# power_24V.net
KiCad netlist of a schematic drawn in Altium Designer
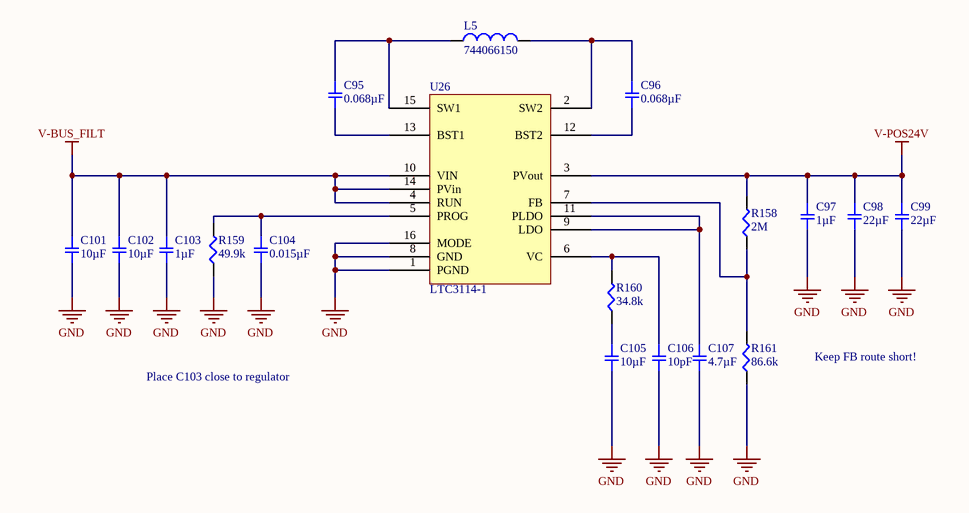
[diagram p0: power_24V.SchDoc]

(export (version "E")
  (design (tool "Eeschema 10.0.6"))
  (components
    (comp (ref "C95")
      (value "0.068µF")
      (footprint "SMD-0805C")
      (description "CAP CER 0.068UF 50V X7R 0805")
      (fields
        (field (name "DIGI-KEY PART NUMBER") "490-5807-1-ND")
        (field (name "PART NUMBER") "GCJ21BR71H683KA01L")
      )
      (libsource (lib "capacitors") (part "GCJ21BR71H683KA01L"))
    )
    (comp (ref "C96")
      (value "0.068µF")
      (footprint "SMD-0805C")
      (description "CAP CER 0.068UF 50V X7R 0805")
      (fields
        (field (name "DIGI-KEY PART NUMBER") "490-5807-1-ND")
        (field (name "PART NUMBER") "GCJ21BR71H683KA01L")
      )
      (libsource (lib "capacitors") (part "GCJ21BR71H683KA01L"))
    )
    (comp (ref "C97")
      (value "1µF")
      (footprint "SMD-0805C")
      (description "CAP CER 1UF 50V X7R 0805")
      (fields
        (field (name "DIGI-KEY PART NUMBER") "490-10667-1-ND")
        (field (name "PART NUMBER") "GCJ21BR71H105KA01L")
      )
      (libsource (lib "capacitors") (part "GCJ21BR71H105KA01L"))
    )
    (comp (ref "C98")
      (value "22µF")
      (footprint "SMD-1206C")
      (description "CAP CER 22UF 25V X5R 1206")
      (fields
        (field (name "DIGI-KEY PART NUMBER") "490-5527-1-ND")
        (field (name "PART NUMBER") "GRM31CR61E226KE15L")
      )
      (libsource (lib "capacitors") (part "GRM31CR61E226KE15L"))
    )
    (comp (ref "C99")
      (value "22µF")
      (footprint "SMD-1206C")
      (description "CAP CER 22UF 25V X5R 1206")
      (fields
        (field (name "DIGI-KEY PART NUMBER") "490-5527-1-ND")
        (field (name "PART NUMBER") "GRM31CR61E226KE15L")
      )
      (libsource (lib "capacitors") (part "GRM31CR61E226KE15L"))
    )
    (comp (ref "C101")
      (value "10µF")
      (footprint "SMD-1206C")
      (description "CAP CER 10UF 50V X5R 1206")
      (fields
        (field (name "DIGI-KEY PART NUMBER") "490-5961-1-ND")
        (field (name "PART NUMBER") "GRM31CR61H106KA12L")
      )
      (libsource (lib "capacitors") (part "GRM31CR61H106KA12L"))
    )
    (comp (ref "C102")
      (value "10µF")
      (footprint "SMD-1206C")
      (description "CAP CER 10UF 50V X5R 1206")
      (fields
        (field (name "DIGI-KEY PART NUMBER") "490-5961-1-ND")
        (field (name "PART NUMBER") "GRM31CR61H106KA12L")
      )
      (libsource (lib "capacitors") (part "GRM31CR61H106KA12L"))
    )
    (comp (ref "C103")
      (value "1µF")
      (footprint "SMD-1206C")
      (description "CAP CER 1UF 50V X7R 1206")
      (fields
        (field (name "DIGI-KEY PART NUMBER") "490-5810-1-ND")
        (field (name "PART NUMBER") "GCJ31MR71H105KA12L")
      )
      (libsource (lib "capacitors") (part "GCJ31MR71H105KA12L"))
    )
    (comp (ref "C104")
      (value "0.015µF")
      (footprint "SMD-0805C")
      (description "CAP CER 0.015UF 250V X7T 0805")
      (fields
        (field (name "DIGI-KEY PART NUMBER") "490-13987-1-ND")
        (field (name "PART NUMBER") "GC321AD72E153KX01D")
      )
      (libsource (lib "capacitors") (part "GC321AD72E153KX01D"))
    )
    (comp (ref "C105")
      (value "10µF")
      (footprint "SMD-1206C")
      (description "CAP CER 10UF 50V X5R 1206")
      (fields
        (field (name "DIGI-KEY PART NUMBER") "490-5961-1-ND")
        (field (name "PART NUMBER") "GRM31CR61H106KA12L")
      )
      (libsource (lib "capacitors") (part "GRM31CR61H106KA12L"))
    )
    (comp (ref "C106")
      (value "10pF")
      (footprint "SMD-0805C")
      (description "CAP CER 10PF 100V NP0 0805")
      (fields
        (field (name "DIGI-KEY PART NUMBER") "490-6098-1-ND")
        (field (name "PART NUMBER") "GQM2195C2A100GB01D")
      )
      (libsource (lib "capacitors") (part "GQM2195C2A100GB01D"))
    )
    (comp (ref "C107")
      (value "4.7µF")
      (footprint "SMD-1206C")
      (description "CAP CER 4.7UF 50V X7S 1206")
      (fields
        (field (name "DIGI-KEY PART NUMBER") "490-11167-1-ND")
        (field (name "PART NUMBER") "GCM31CC71H475KA03L")
      )
      (libsource (lib "capacitors") (part "GCM31CC71H475KA03L"))
    )
    (comp (ref "L5")
      (value "744066150")
      (footprint "INDP100100X38N")
      (description "FIXED IND 15UH 3.2A 50 MOHM SMD")
      (fields (field (name "MANUFACTURER") "Wurth Electronics") (field (name "TOLERANCE") "30%"))
      (libsource (lib "inductor") (part "744066150"))
    )
    (comp (ref "R158")
      (value "2M")
      (footprint "SMD-0805-RES")
      (description "RES SMD 2M OHM 1% 1/8W 0805")
      (fields
        (field (name "PART NUMBER") "ERJ-6ENF2004V")
        (field (name "DIGI-KEY PART NUMBER") "P2.00MCCT-ND")
      )
      (libsource (lib "resistors") (part "ERJ-6ENF2004V"))
    )
    (comp (ref "R159")
      (value "49.9k")
      (footprint "SMD-0805-RES")
      (description "RES SMD 49.9K OHM 1% 1/8W 0805")
      (fields
        (field (name "PART NUMBER") "ERJ-6ENF4992V")
        (field (name "DIGI-KEY PART NUMBER") "P49.9KCCT-ND")
      )
      (libsource (lib "resistors") (part "ERJ-6ENF4992V"))
    )
    (comp (ref "R160")
      (value "34.8k")
      (footprint "SMD-0805-RES")
      (description "RES SMD 34.8K OHM 1% 1/8W 0805")
      (fields
        (field (name "PART NUMBER") "ERJ-6ENF3482V")
        (field (name "DIGI-KEY PART NUMBER") "P34.8KCCT-ND")
      )
      (libsource (lib "resistors") (part "ERJ-6ENF3482V"))
    )
    (comp (ref "R161")
      (value "86.6k")
      (footprint "SMD-0805-RES")
      (description "RES SMD 86.6K OHM 1% 1/8W 0805")
      (fields
        (field (name "PART NUMBER") "ERJ-6ENF8662V")
        (field (name "DIGI-KEY PART NUMBER") "P86.6KCCT-ND")
      )
      (libsource (lib "resistors") (part "ERJ-6ENF8662V"))
    )
    (comp (ref "U26")
      (value "LTC3114-1")
      (footprint "TSOP65P640X110_HS-17N")
      (fields
        (field (name "MANUFACTURER") "Analog Devices / Linear Technology")
        (field (name "MANUFACTURER PART NUMBER") "LTC3114EFE-1#TRPBF")
      )
      (libsource (lib "ic") (part "LTC3114-1"))
    )
  )
  (nets
    (net (code "1") (name "GND") (class "Default")
      (node (ref "C101") (pin "2") (pinfunction "2_2") (pintype "passive"))
      (node (ref "C102") (pin "2") (pinfunction "2_2") (pintype "passive"))
      (node (ref "C103") (pin "2") (pinfunction "2_2") (pintype "passive"))
      (node (ref "C104") (pin "2") (pinfunction "2_2") (pintype "passive"))
      (node (ref "C105") (pin "2") (pinfunction "2_2") (pintype "passive"))
      (node (ref "C106") (pin "2") (pinfunction "2_2") (pintype "passive"))
      (node (ref "C107") (pin "2") (pinfunction "2_2") (pintype "passive"))
      (node (ref "C97") (pin "2") (pinfunction "2_2") (pintype "passive"))
      (node (ref "C98") (pin "2") (pinfunction "2_2") (pintype "passive"))
      (node (ref "C99") (pin "2") (pinfunction "2_2") (pintype "passive"))
      (node (ref "R159") (pin "1") (pinfunction "1_1") (pintype "passive"))
      (node (ref "R161") (pin "1") (pinfunction "1_1") (pintype "passive"))
      (node (ref "U26") (pin "1") (pinfunction "PGND_1") (pintype "passive"))
      (node (ref "U26") (pin "16") (pinfunction "MODE_16") (pintype "passive"))
      (node (ref "U26") (pin "8") (pinfunction "GND_8") (pintype "passive"))
    )
    (net (code "2") (name "Net-(C105-Pad1)") (class "Default")
      (node (ref "C105") (pin "1") (pinfunction "1_1") (pintype "passive"))
      (node (ref "R160") (pin "1") (pinfunction "1_1") (pintype "passive"))
    )
    (net (code "3") (name "Net-(U26-BST1)") (class "Default")
      (node (ref "C95") (pin "2") (pinfunction "2_2") (pintype "passive"))
      (node (ref "U26") (pin "13") (pinfunction "BST1_13") (pintype "passive"))
    )
    (net (code "4") (name "Net-(U26-BST2)") (class "Default")
      (node (ref "C96") (pin "2") (pinfunction "2_2") (pintype "passive"))
      (node (ref "U26") (pin "12") (pinfunction "BST2_12") (pintype "passive"))
    )
    (net (code "5") (name "Net-(U26-FB)") (class "Default")
      (node (ref "R158") (pin "1") (pinfunction "1_1") (pintype "passive"))
      (node (ref "R161") (pin "2") (pinfunction "2_2") (pintype "passive"))
      (node (ref "U26") (pin "7") (pinfunction "FB_7") (pintype "passive"))
    )
    (net (code "6") (name "Net-(U26-LDO)") (class "Default")
      (node (ref "C107") (pin "1") (pinfunction "1_1") (pintype "passive"))
      (node (ref "U26") (pin "11") (pinfunction "PLDO_11") (pintype "passive"))
      (node (ref "U26") (pin "9") (pinfunction "LDO_9") (pintype "passive"))
    )
    (net (code "7") (name "Net-(U26-PROG)") (class "Default")
      (node (ref "C104") (pin "1") (pinfunction "1_1") (pintype "passive"))
      (node (ref "R159") (pin "2") (pinfunction "2_2") (pintype "passive"))
      (node (ref "U26") (pin "5") (pinfunction "PROG_5") (pintype "passive"))
    )
    (net (code "8") (name "Net-(U26-SW1)") (class "Default")
      (node (ref "C95") (pin "1") (pinfunction "1_1") (pintype "passive"))
      (node (ref "L5") (pin "1") (pinfunction "1_1") (pintype "passive"))
      (node (ref "U26") (pin "15") (pinfunction "SW1_15") (pintype "passive"))
    )
    (net (code "9") (name "Net-(U26-SW2)") (class "Default")
      (node (ref "C96") (pin "1") (pinfunction "1_1") (pintype "passive"))
      (node (ref "L5") (pin "2") (pinfunction "2_2") (pintype "passive"))
      (node (ref "U26") (pin "2") (pinfunction "SW2_2") (pintype "passive"))
    )
    (net (code "10") (name "Net-(U26-VC)") (class "Default")
      (node (ref "C106") (pin "1") (pinfunction "1_1") (pintype "passive"))
      (node (ref "R160") (pin "2") (pinfunction "2_2") (pintype "passive"))
      (node (ref "U26") (pin "6") (pinfunction "VC_6") (pintype "passive"))
    )
    (net (code "11") (name "V-BUS_FILT") (class "Default")
      (node (ref "C101") (pin "1") (pinfunction "1_1") (pintype "passive"))
      (node (ref "C102") (pin "1") (pinfunction "1_1") (pintype "passive"))
      (node (ref "C103") (pin "1") (pinfunction "1_1") (pintype "passive"))
      (node (ref "U26") (pin "10") (pinfunction "VIN_10") (pintype "passive"))
      (node (ref "U26") (pin "14") (pinfunction "PVin_14") (pintype "passive"))
      (node (ref "U26") (pin "4") (pinfunction "RUN_4") (pintype "passive"))
    )
    (net (code "12") (name "V-POS24V") (class "Default")
      (node (ref "C97") (pin "1") (pinfunction "1_1") (pintype "passive"))
      (node (ref "C98") (pin "1") (pinfunction "1_1") (pintype "passive"))
      (node (ref "C99") (pin "1") (pinfunction "1_1") (pintype "passive"))
      (node (ref "R158") (pin "2") (pinfunction "2_2") (pintype "passive"))
      (node (ref "U26") (pin "3") (pinfunction "PVout_3") (pintype "passive"))
    )
  )
)
